# 04_IMU.net
KiCad netlist of a schematic drawn in Altium Designer
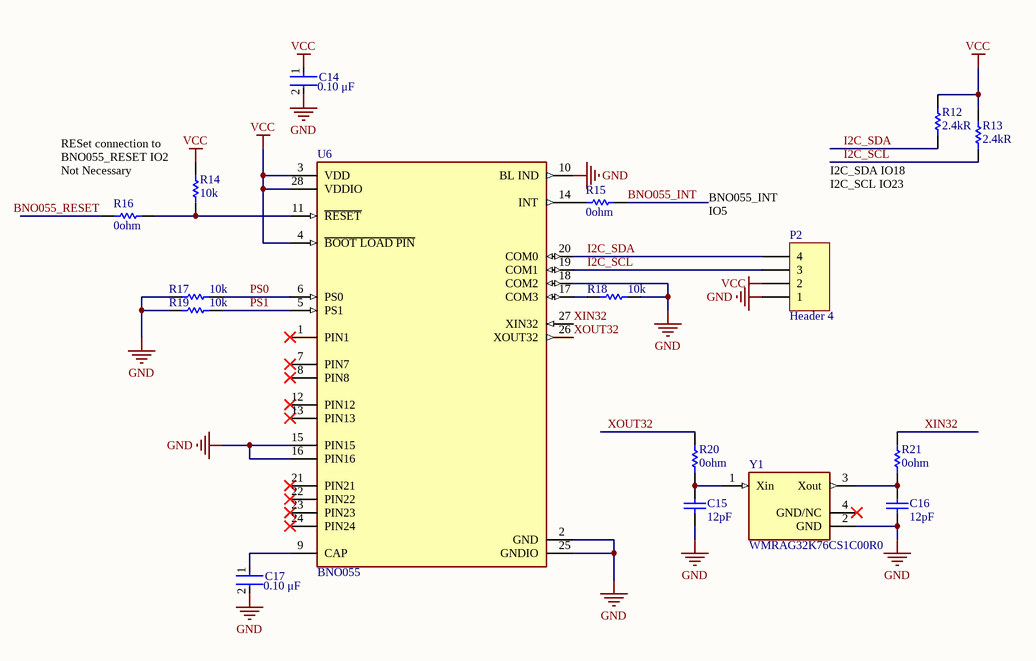
[diagram p0: 04_IMU.SchDoc]

(export (version "E")
  (design (tool "Eeschema 10.0.6"))
  (components
    (comp (ref "C14")
      (value "C0603C104M4RAC7411")
      (footprint "FP-C0603C-CF-MFG")
      (description "CAP CER 0.1UF 16V X7R 0603")
      (fields
        (field (name "TOLERANCE") "0.2")
        (field (name "CAPACITANCE") "0.10 μF")
        (field (name "MANUFACTURER") "KEMET")
      )
      (libsource (lib "Altium Content Vault") (part "b4654b650e69147ec39a6b967a45e02"))
    )
    (comp (ref "C15")
      (value "12pF")
      (footprint "CAPC1608X90X40NL10T20")
      (description "Chip Capacitor, 12 pF, +/- 5%, 50 V, -55 to 125 degC, 0603 (1608 Metric), RoHS, Tape and Reel")
      (fields (field (name "TOLERANCE") "1%") (field (name "Comment") "CC0603JRNPO9BN120"))
      (libsource (lib "Altium Content Vault") (part "CAP-NP-2"))
    )
    (comp (ref "C16")
      (value "12pF")
      (footprint "CAPC1608X90X40NL10T20")
      (description "Chip Capacitor, 12 pF, +/- 5%, 50 V, -55 to 125 degC, 0603 (1608 Metric), RoHS, Tape and Reel")
      (fields (field (name "TOLERANCE") "1%") (field (name "Comment") "CC0603JRNPO9BN120"))
      (libsource (lib "Altium Content Vault") (part "CAP-NP-2"))
    )
    (comp (ref "C17")
      (value "C0603C104M4RAC7411")
      (footprint "FP-C0603C-CF-MFG")
      (description "CAP CER 0.1UF 16V X7R 0603")
      (fields
        (field (name "TOLERANCE") "0.2")
        (field (name "CAPACITANCE") "0.10 μF")
        (field (name "MANUFACTURER") "KEMET")
      )
      (libsource (lib "Altium Content Vault") (part "b4654b650e69147ec39a6b967a45e02"))
    )
    (comp (ref "P2")
      (value "Header 4")
      (footprint "HDR1X4")
      (description "Header, 4-Pin")
      (fields (field (name "PUBLISHER") "Altium Limited"))
      (libsource (lib "Miscellaneous Connectors") (part "Header 4"))
    )
    (comp (ref "R12")
      (value "2.4kR")
      (footprint "RESC1608X50X30ML20T20")
      (fields (field (name "PART NUMBER") "RR0816P-242-D") (field (name "MANUFACTURER") "Susumu"))
      (libsource (lib "Altium Content Vault") (part "RES"))
    )
    (comp (ref "R13")
      (value "2.4kR")
      (footprint "RESC1608X50X30ML20T20")
      (fields (field (name "PART NUMBER") "RR0816P-242-D") (field (name "MANUFACTURER") "Susumu"))
      (libsource (lib "Altium Content Vault") (part "RES"))
    )
    (comp (ref "R14")
      (value "10k")
      (footprint "RESC1609X55X30LL15T15")
      (description "Chip Resistor, 10 KOhm, +/- 1%, 0.1 W, -55 to 155 degC, 0603 (1608 Metric), RoHS, Tape and Reel")
      (fields (field (name "TOLERANCE") "1%") (field (name "MANUFACTURER") "Panasonic"))
      (libsource (lib "Altium Content Vault") (part "RES-2"))
    )
    (comp (ref "R15")
      (value "0ohm")
      (footprint "RESC1608X55X25ML10T15")
      (description "Chip Resistor, 0 Ohm, +/- 5%, 0.1 W, -55 to 155 degC, 0603 (1608 Metric), RoHS, Tape and Reel")
      (fields (field (name "TOLERANCE") "5%") (field (name "MANUFACTURER") "Yageo"))
      (libsource (lib "Altium Content Vault") (part "RES-2"))
    )
    (comp (ref "R16")
      (value "0ohm")
      (footprint "RESC1608X55X25ML10T15")
      (description "Chip Resistor, 0 Ohm, +/- 5%, 0.1 W, -55 to 155 degC, 0603 (1608 Metric), RoHS, Tape and Reel")
      (fields (field (name "TOLERANCE") "5%") (field (name "MANUFACTURER") "Yageo"))
      (libsource (lib "Altium Content Vault") (part "RES-2"))
    )
    (comp (ref "R17")
      (value "10k")
      (footprint "RESC1609X55X30LL15T15")
      (description "Chip Resistor, 10 KOhm, +/- 1%, 0.1 W, -55 to 155 degC, 0603 (1608 Metric), RoHS, Tape and Reel")
      (fields (field (name "TOLERANCE") "1%") (field (name "MANUFACTURER") "Panasonic"))
      (libsource (lib "Altium Content Vault") (part "RES-2"))
    )
    (comp (ref "R18")
      (value "10k")
      (footprint "RESC1609X55X30LL15T15")
      (description "Chip Resistor, 10 KOhm, +/- 1%, 0.1 W, -55 to 155 degC, 0603 (1608 Metric), RoHS, Tape and Reel")
      (fields (field (name "TOLERANCE") "1%") (field (name "MANUFACTURER") "Panasonic"))
      (libsource (lib "Altium Content Vault") (part "RES-2"))
    )
    (comp (ref "R19")
      (value "10k")
      (footprint "RESC1609X55X30LL15T15")
      (description "Chip Resistor, 10 KOhm, +/- 1%, 0.1 W, -55 to 155 degC, 0603 (1608 Metric), RoHS, Tape and Reel")
      (fields (field (name "TOLERANCE") "1%") (field (name "MANUFACTURER") "Panasonic"))
      (libsource (lib "Altium Content Vault") (part "RES-2"))
    )
    (comp (ref "R20")
      (value "0ohm")
      (footprint "RESC1608X55X25ML10T15")
      (description "Chip Resistor, 0 Ohm, +/- 5%, 0.1 W, -55 to 155 degC, 0603 (1608 Metric), RoHS, Tape and Reel")
      (fields (field (name "TOLERANCE") "5%") (field (name "MANUFACTURER") "Yageo"))
      (libsource (lib "Altium Content Vault") (part "RES-2"))
    )
    (comp (ref "R21")
      (value "0ohm")
      (footprint "RESC1608X55X25ML10T15")
      (description "Chip Resistor, 0 Ohm, +/- 5%, 0.1 W, -55 to 155 degC, 0603 (1608 Metric), RoHS, Tape and Reel")
      (fields (field (name "TOLERANCE") "5%") (field (name "MANUFACTURER") "Yageo"))
      (libsource (lib "Altium Content Vault") (part "RES-2"))
    )
    (comp (ref "U6")
      (value "BNO055")
      (footprint "FP-BNO055-MFG")
      (description "IMU ACCEL/GYRO/MAG I2C 28LGA")
      (fields
        (field (name "OCTOPART") "https://octopart.com/bno055-bosch+sensortec-50309911")
        (field (name "VOLTAGE") "1.7~3.6V")
      )
      (libsource (lib "Altium Content Vault") (part "72d621e61db15910e840a84e68b4f76"))
    )
    (comp (ref "Y1")
      (value "WMRAG32K76CS1C00R0")
      (footprint "FP-WMRAG32K76CS1C00R0-MFG")
      (description "MEMS Resonator")
      (fields (field (name "TOLERANCE") "20ppm") (field (name "MANUFACTURER") "Murata"))
      (libsource (lib "Altium Content Vault") (part "f3e38fa55a21b72a83ee03d0b531324"))
    )
  )
  (nets
    (net (code "1") (name "/BNO055_INT") (class "Default")
      (node (ref "R15") (pin "2") (pinfunction "2_2") (pintype "passive"))
    )
    (net (code "2") (name "/BNO055_RESET") (class "Default")
      (node (ref "R16") (pin "1") (pinfunction "1_1") (pintype "passive"))
    )
    (net (code "3") (name "/I2C_SCL") (class "Default")
      (node (ref "P2") (pin "3") (pinfunction "3_3") (pintype "passive"))
      (node (ref "R13") (pin "1") (pinfunction "1_1") (pintype "passive"))
      (node (ref "U6") (pin "19") (pinfunction "COM1_19") (pintype "bidirectional"))
    )
    (net (code "4") (name "/I2C_SDA") (class "Default")
      (node (ref "P2") (pin "4") (pinfunction "4_4") (pintype "passive"))
      (node (ref "R12") (pin "1") (pinfunction "1_1") (pintype "passive"))
      (node (ref "U6") (pin "20") (pinfunction "COM0_20") (pintype "bidirectional"))
    )
    (net (code "5") (name "/PS0") (class "Default")
      (node (ref "R17") (pin "2") (pinfunction "2_2") (pintype "passive"))
      (node (ref "U6") (pin "6") (pinfunction "PS0_6") (pintype "input"))
    )
    (net (code "6") (name "/PS1") (class "Default")
      (node (ref "R19") (pin "2") (pinfunction "2_2") (pintype "passive"))
      (node (ref "U6") (pin "5") (pinfunction "PS1_5") (pintype "input"))
    )
    (net (code "7") (name "/XIN32") (class "Default")
      (node (ref "R21") (pin "1") (pinfunction "1_1") (pintype "passive"))
      (node (ref "U6") (pin "27") (pinfunction "XIN32_27") (pintype "input"))
    )
    (net (code "8") (name "/XOUT32") (class "Default")
      (node (ref "R20") (pin "1") (pinfunction "1_1") (pintype "passive"))
      (node (ref "U6") (pin "26") (pinfunction "XOUT32_26") (pintype "output"))
    )
    (net (code "9") (name "GND") (class "Default")
      (node (ref "C14") (pin "2") (pinfunction "2_2") (pintype "passive"))
      (node (ref "C15") (pin "1") (pinfunction "1_1") (pintype "passive"))
      (node (ref "C16") (pin "1") (pinfunction "1_1") (pintype "passive"))
      (node (ref "C17") (pin "2") (pinfunction "2_2") (pintype "passive"))
      (node (ref "P2") (pin "1") (pinfunction "1_1") (pintype "passive"))
      (node (ref "R17") (pin "1") (pinfunction "1_1") (pintype "passive"))
      (node (ref "R18") (pin "1") (pinfunction "1_1") (pintype "passive"))
      (node (ref "R19") (pin "1") (pinfunction "1_1") (pintype "passive"))
      (node (ref "U6") (pin "10") (pinfunction "BL_IND_10") (pintype "output"))
      (node (ref "U6") (pin "15") (pinfunction "PIN15_15") (pintype "power_in"))
      (node (ref "U6") (pin "16") (pinfunction "PIN16_16") (pintype "power_in"))
      (node (ref "U6") (pin "18") (pinfunction "COM2_18") (pintype "bidirectional"))
      (node (ref "U6") (pin "2") (pinfunction "GND_2") (pintype "power_in"))
      (node (ref "U6") (pin "25") (pinfunction "GNDIO_25") (pintype "power_in"))
      (node (ref "Y1") (pin "2") (pinfunction "GND_2") (pintype "power_in"))
    )
    (net (code "10") (name "Net-(U6-CAP)") (class "Default")
      (node (ref "C17") (pin "1") (pinfunction "1_1") (pintype "passive"))
      (node (ref "U6") (pin "9") (pinfunction "CAP_9") (pintype "passive"))
    )
    (net (code "11") (name "Net-(U6-COM3)") (class "Default")
      (node (ref "R18") (pin "2") (pinfunction "2_2") (pintype "passive"))
      (node (ref "U6") (pin "17") (pinfunction "COM3_17") (pintype "bidirectional"))
    )
    (net (code "12") (name "Net-(U6-INT)") (class "Default")
      (node (ref "R15") (pin "1") (pinfunction "1_1") (pintype "passive"))
      (node (ref "U6") (pin "14") (pinfunction "INT_14") (pintype "output"))
    )
    (net (code "13") (name "Net-(U6-~{RESET})") (class "Default")
      (node (ref "R14") (pin "1") (pinfunction "1_1") (pintype "passive"))
      (node (ref "R16") (pin "2") (pinfunction "2_2") (pintype "passive"))
      (node (ref "U6") (pin "11") (pinfunction "~{RESET}_11") (pintype "input"))
    )
    (net (code "14") (name "Net-(Y1-Xin)") (class "Default")
      (node (ref "C15") (pin "2") (pinfunction "2_2") (pintype "passive"))
      (node (ref "R20") (pin "2") (pinfunction "2_2") (pintype "passive"))
      (node (ref "Y1") (pin "1") (pinfunction "Xin_1") (pintype "input"))
    )
    (net (code "15") (name "Net-(Y1-Xout)") (class "Default")
      (node (ref "C16") (pin "2") (pinfunction "2_2") (pintype "passive"))
      (node (ref "R21") (pin "2") (pinfunction "2_2") (pintype "passive"))
      (node (ref "Y1") (pin "3") (pinfunction "Xout_3") (pintype "output"))
    )
    (net (code "16") (name "VCC") (class "Default")
      (node (ref "C14") (pin "1") (pinfunction "1_1") (pintype "passive"))
      (node (ref "P2") (pin "2") (pinfunction "2_2") (pintype "passive"))
      (node (ref "R12") (pin "2") (pinfunction "2_2") (pintype "passive"))
      (node (ref "R13") (pin "2") (pinfunction "2_2") (pintype "passive"))
      (node (ref "R14") (pin "2") (pinfunction "2_2") (pintype "passive"))
      (node (ref "U6") (pin "28") (pinfunction "VDDIO_28") (pintype "power_in"))
      (node (ref "U6") (pin "3") (pinfunction "VDD_3") (pintype "power_in"))
      (node (ref "U6") (pin "4") (pinfunction "~{BOOT_LOAD_PIN}_4") (pintype "input"))
    )
    (net (code "17") (name "unconnected-(U6-PIN1-Pad1)") (class "Default")
      (node (ref "U6") (pin "1") (pinfunction "PIN1_1") (pintype "passive+no_connect"))
    )
    (net (code "18") (name "unconnected-(U6-PIN7-Pad7)") (class "Default")
      (node (ref "U6") (pin "7") (pinfunction "PIN7_7") (pintype "passive+no_connect"))
    )
    (net (code "19") (name "unconnected-(U6-PIN8-Pad8)") (class "Default")
      (node (ref "U6") (pin "8") (pinfunction "PIN8_8") (pintype "passive+no_connect"))
    )
    (net (code "20") (name "unconnected-(U6-PIN12-Pad12)") (class "Default")
      (node (ref "U6") (pin "12") (pinfunction "PIN12_12") (pintype "passive+no_connect"))
    )
    (net (code "21") (name "unconnected-(U6-PIN13-Pad13)") (class "Default")
      (node (ref "U6") (pin "13") (pinfunction "PIN13_13") (pintype "passive+no_connect"))
    )
    (net (code "22") (name "unconnected-(U6-PIN21-Pad21)") (class "Default")
      (node (ref "U6") (pin "21") (pinfunction "PIN21_21") (pintype "passive+no_connect"))
    )
    (net (code "23") (name "unconnected-(U6-PIN22-Pad22)") (class "Default")
      (node (ref "U6") (pin "22") (pinfunction "PIN22_22") (pintype "passive+no_connect"))
    )
    (net (code "24") (name "unconnected-(U6-PIN23-Pad23)") (class "Default")
      (node (ref "U6") (pin "23") (pinfunction "PIN23_23") (pintype "passive+no_connect"))
    )
    (net (code "25") (name "unconnected-(U6-PIN24-Pad24)") (class "Default")
      (node (ref "U6") (pin "24") (pinfunction "PIN24_24") (pintype "passive+no_connect"))
    )
    (net (code "26") (name "unconnected-(Y1-GND{slash}NC-Pad4)") (class "Default")
      (node (ref "Y1") (pin "4") (pinfunction "GND/NC_4") (pintype "passive+no_connect"))
    )
  )
)
